# 08_USB_OTG_POWER.net
KiCad netlist of a schematic drawn in Altium Designer
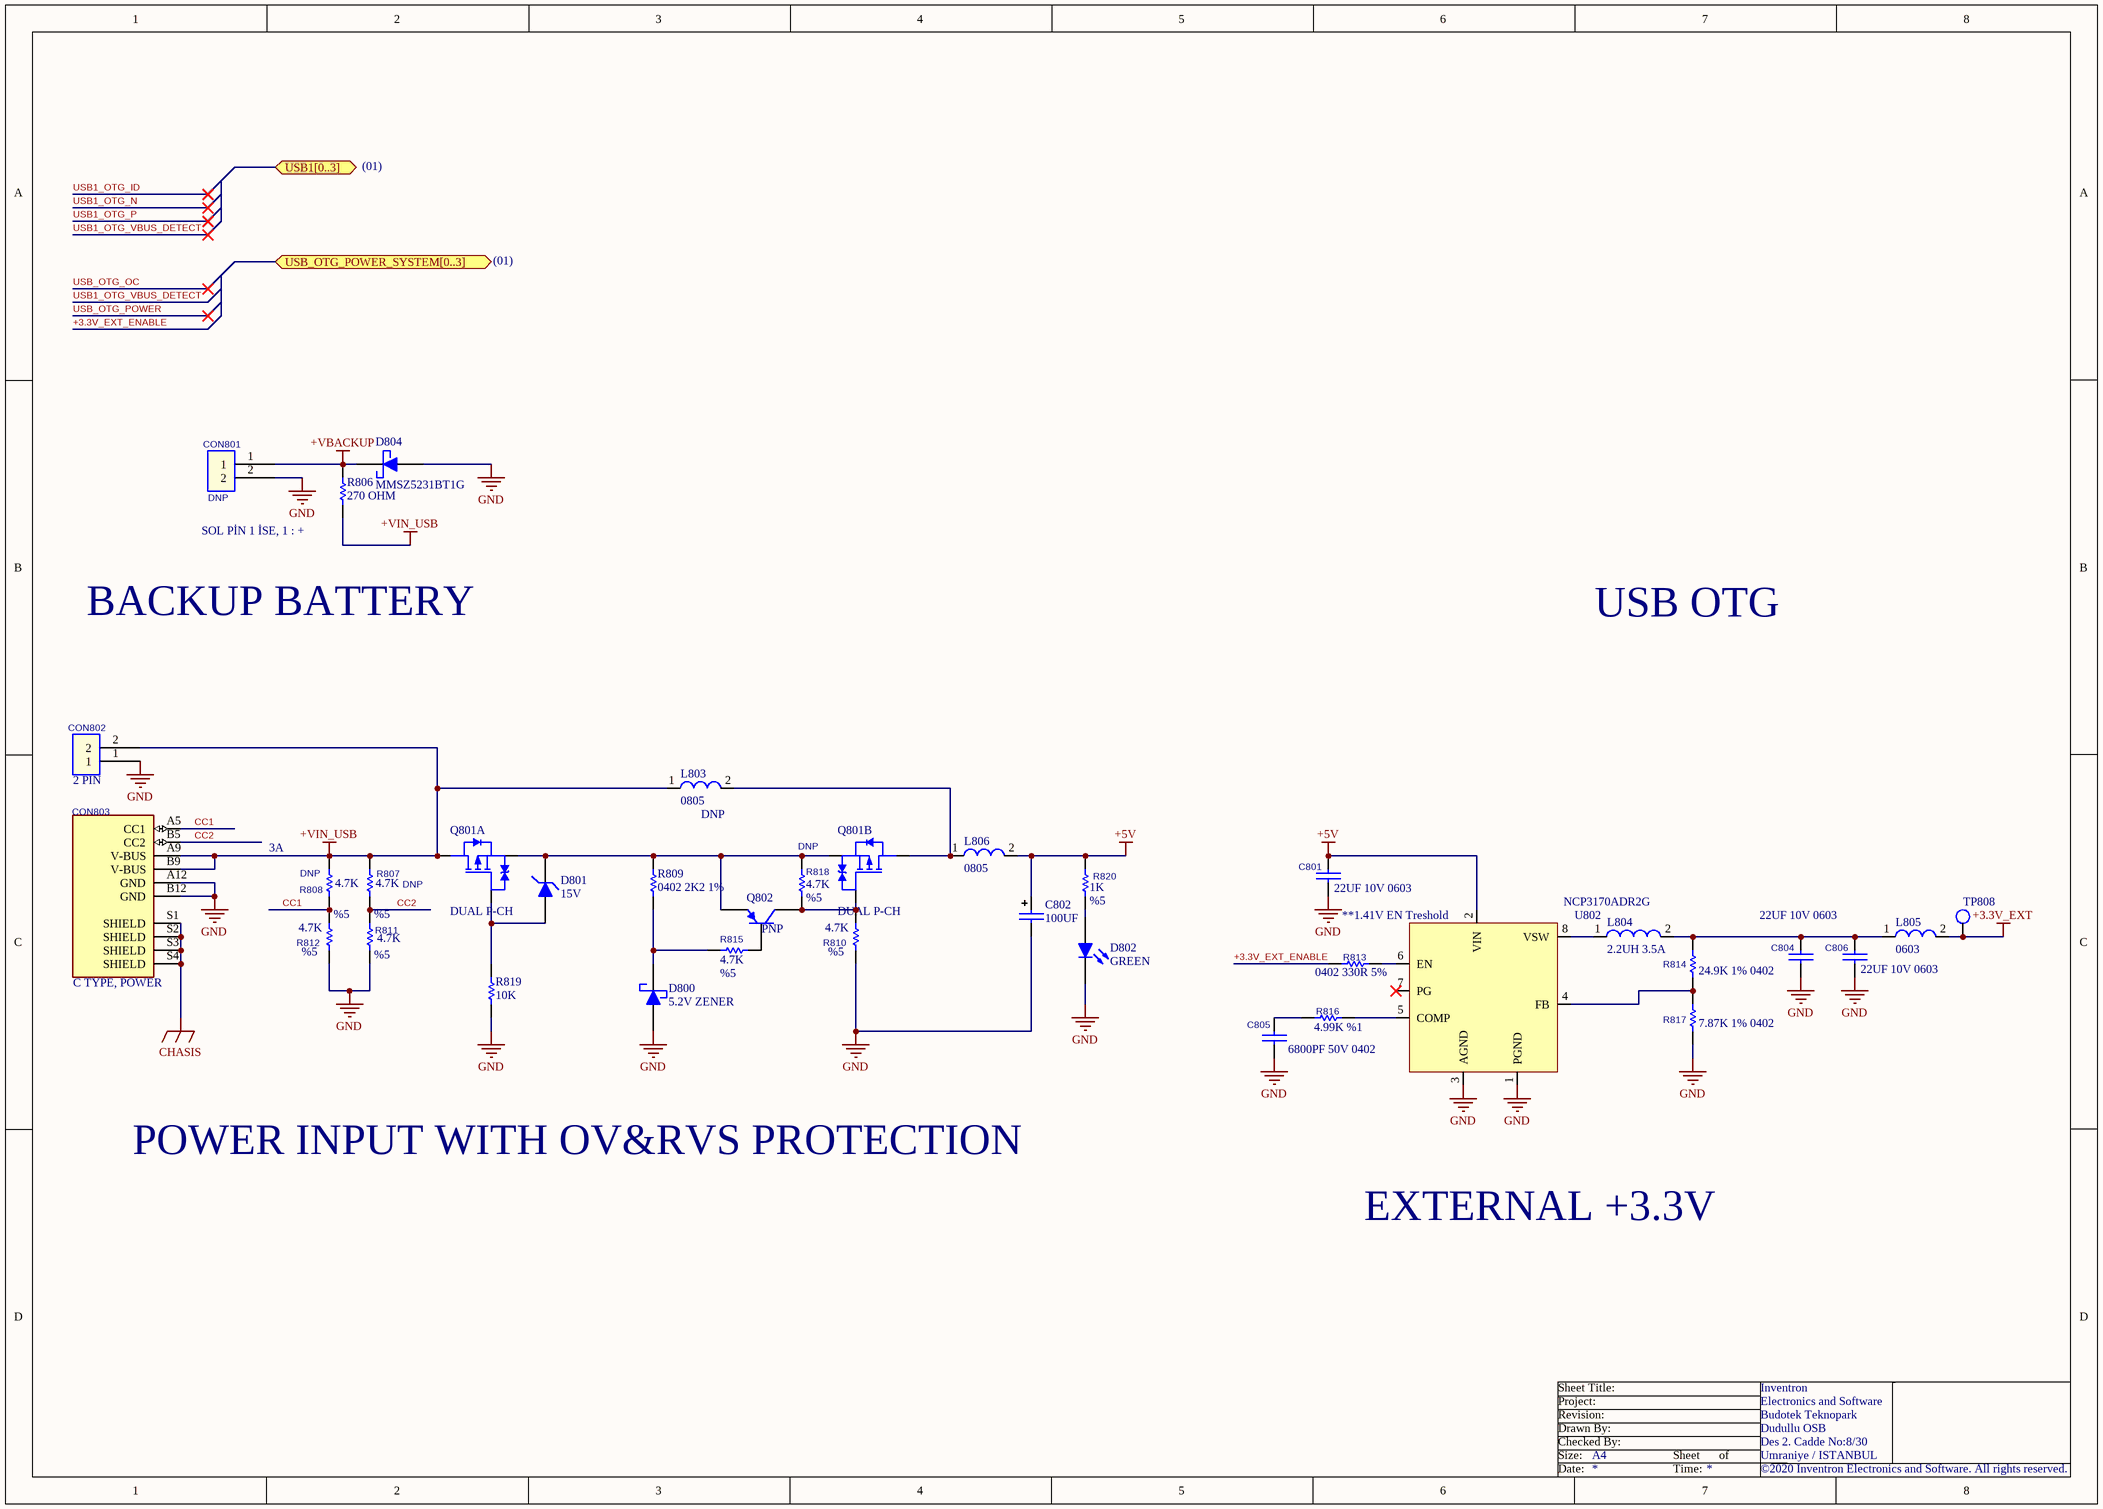
[diagram p0: 08 USB OTG & POWER.SchDoc]

(export (version "E")
  (design (tool "Eeschema 10.0.6"))
  (components
    (comp (ref "C801")
      (value "22UF 10V 0603")
      (footprint "0603_CC")
      (description "±20% 10V Ceramic Capacitor X5R 0603 (1608 Metric)")
      (fields (field (name "CREATED BY") "E.E") (field (name "CHECKED BY") "*"))
      (libsource (lib "ARETE_SCH") (part "CAP-C1608X5R1A226M080AC"))
    )
    (comp (ref "C802")
      (value "100UF")
      (footprint "UWR1A101MCL1GB")
      (description "CAP ALUM 100UF 20% 10V SMD")
      (fields (field (name "CREATED BY") "EE") (field (name "CHECKED BY") "*"))
      (libsource (lib "ARETE_V2_SCH") (part "CAP-UWR1A101MCL1GB"))
    )
    (comp (ref "C804")
      (value "22UF 10V 0603")
      (footprint "0603_CC")
      (description "±20% 10V Ceramic Capacitor X5R 0603 (1608 Metric)")
      (fields (field (name "CREATED BY") "E.E") (field (name "CHECKED BY") "*"))
      (libsource (lib "ARETE_SCH") (part "CAP-C1608X5R1A226M080AC"))
    )
    (comp (ref "C805")
      (value "6800PF 50V 0402")
      (footprint "0402_CC")
      (description "6800pF ±10% 50V Ceramic Capacitor X7R 0402 (1005 Metric)")
      (fields (field (name "CREATED BY") "E.E") (field (name "CHECKED BY") "*"))
      (libsource (lib "ARETE_SCH") (part "CAP-CL05B682KB5NNNC"))
    )
    (comp (ref "C806")
      (value "22UF 10V 0603")
      (footprint "0603_CC")
      (description "±20% 10V Ceramic Capacitor X5R 0603 (1608 Metric)")
      (fields (field (name "CREATED BY") "E.E") (field (name "CHECKED BY") "*"))
      (libsource (lib "ARETE_SCH") (part "CAP-C1608X5R1A226M080AC"))
    )
    (comp (ref "CON801")
      (value "CON-B2B-PH-K-S(LF)(SN)")
      (footprint "B2B-PH-K-S")
      (description "CONN HEADER VERT 2POS 2MM")
      (fields
        (field (name "ASSY_OPT") "DNP")
        (field (name "CREATED BY") "LA")
        (field (name "CHECKED BY") "*")
      )
      (libsource (lib "ARETE_L") (part "CON-B2B-PH-K-S(LF)(SN)"))
    )
    (comp (ref "CON802")
      (value "2 PIN")
      (footprint "640456-2")
      (description "CONN HEADER VERT 2POS 2.54MM")
      (fields (field (name "CREATED BY") "LA") (field (name "CHECKED BY") "*"))
      (libsource (lib "ARETE_L") (part "CON-640456-2"))
    )
    (comp (ref "CON803")
      (value "C TYPE, POWER")
      (footprint "CUI_UJC-HP-3-SMT-TR")
      (description "USB JACK, C TYPE, POWER ONLY, 6")
      (fields (field (name "CREATED BY") "E.E") (field (name "CHECKED BY") "*"))
      (libsource (lib "ARETE_SCH") (part "0-CON-UJC-HP-3-SMT-TR"))
    )
    (comp (ref "D800")
      (value "5.2V ZENER")
      (footprint "SOD-323")
      (description "DIODE ZENER 5.1V 320MW SOD323")
      (fields (field (name "CREATED BY") "EE") (field (name "CHECKED BY") "*"))
      (libsource (lib "ARETE_V2_SCH") (part "DIODE-PZU5.1B2A,115"))
    )
    (comp (ref "D801")
      (value "15V")
      (footprint "SOD-323")
      (description "DIODE ZENER 15V 400MW SOD323")
      (fields (field (name "CREATED BY") "LA") (field (name "CHECKED BY") "*"))
      (libsource (lib "ARETE_V2_SCH") (part "DIODE-PDZ15B,115"))
    )
    (comp (ref "D802")
      (value "GREEN")
      (footprint "0603_LED")
      (description "LED SMD 0603 SUPER GREEN")
      (fields (field (name "CREATED BY") "*") (field (name "CHECKED BY") "*"))
      (libsource (lib "ARETE_SCH") (part "LED-LTST-C190KRKT"))
    )
    (comp (ref "D804")
      (value "MMSZ5231BT1G")
      (footprint "SOD-123")
      (description "DIODE ZENER 5.1V 500MW SOD123")
      (fields (field (name "CREATED BY") "EE") (field (name "CHECKED BY") "*"))
      (libsource (lib "ARETE_SCH") (part "DIODE-MMSZ5231BT1G"))
    )
    (comp (ref "L803")
      (value "0805")
      (footprint "0805")
      (description "0OHM 0805")
      (fields
        (field (name "ASSY_OPT") "DNP")
        (field (name "CREATED BY") "EE")
        (field (name "CHECKED BY") "*")
      )
      (libsource (lib "ARETE_V2_SCH") (part "IND-FERRITE (RES 0 OHM) 0805"))
    )
    (comp (ref "L804")
      (value "2.2UH 3.5A")
      (footprint "IND-NRS5030T2R2NMGJ")
      (description "Shielded Wirewound Inductor 23mOhm Nonstandard")
      (fields (field (name "CREATED BY") "E.E") (field (name "CHECKED BY") "*"))
      (libsource (lib "ARETE_SCH") (part "IND-NRS5030T2R2NMGJ"))
    )
    (comp (ref "L805")
      (value "0603")
      (footprint "0603_RES")
      (description "0OHM 0603")
      (fields (field (name "CREATED BY") "EE") (field (name "CHECKED BY") "*"))
      (libsource (lib "ARETE_SCH") (part "IND-FERRITE (RES 0 OHM) 0603"))
    )
    (comp (ref "L806")
      (value "0805")
      (footprint "0805")
      (description "0OHM 0805")
      (fields (field (name "CREATED BY") "EE") (field (name "CHECKED BY") "*"))
      (libsource (lib "ARETE_V2_SCH") (part "IND-FERRITE (RES 0 OHM) 0805"))
    )
    (comp (ref "Q801")
      (value "DUAL P-CH")
      (footprint "SO-8 - DUAL MOS - NAMED")
      (description "MOSFET 2P-CH 30V 6A SO-8")
      (fields (field (name "CREATED BY") "*") (field (name "CHECKED BY") "*"))
      (libsource (lib "ARETE_V2_SCH") (part "MOS-P-DMP3028LSD-13"))
    )
    (comp (ref "Q802")
      (value "PNP")
      (footprint "SOT23")
      (description "TRANS PNP 65V 0.1A SOT-23")
      (fields (field (name "CREATED BY") "LA") (field (name "CHECKED BY") "*"))
      (libsource (lib "ARETE_V2_SCH") (part "TRANSISTOR-BC856"))
    )
    (comp (ref "R806")
      (value "270 OHM")
      (footprint "0603_RES")
      (description "RES SMD 270 OHM 5% 1/10W 0603")
      (fields (field (name "CREATED BY") "EE") (field (name "CHECKED BY") "*"))
      (libsource (lib "ARETE_SCH") (part "RES-RC0603JR-07270RL"))
    )
    (comp (ref "R807")
      (value "4.7K")
      (footprint "0402_RES")
      (description "RES 4.7K OHM 5% 1/16W 0402")
      (fields
        (field (name "ASSY_OPT") "DNP")
        (field (name "TOLERANCE") "%5")
        (field (name "CREATED BY") "LA")
        (field (name "CHECKED BY") "*")
      )
      (libsource (lib "ARETE_SCH") (part "RES-4.7K"))
    )
    (comp (ref "R808")
      (value "4.7K")
      (footprint "0402_RES")
      (description "RES 4.7K OHM 5% 1/16W 0402")
      (fields
        (field (name "ASSY_OPT") "DNP")
        (field (name "TOLERANCE") "%5")
        (field (name "CREATED BY") "LA")
        (field (name "CHECKED BY") "*")
      )
      (libsource (lib "ARETE_SCH") (part "RES-4.7K"))
    )
    (comp (ref "R809")
      (value "0402 2K2 1%")
      (footprint "0402_RES")
      (fields (field (name "CREATED BY") "E.E") (field (name "CHECKED BY") "*"))
      (libsource (lib "ARETE_V2_SCH") (part "RES-CRGCQ0402F2K2"))
    )
    (comp (ref "R810")
      (value "4.7K")
      (footprint "0402_RES")
      (description "RES 4.7K OHM 5% 1/16W 0402")
      (fields
        (field (name "TOLERANCE") "%5")
        (field (name "CREATED BY") "LA")
        (field (name "CHECKED BY") "*")
      )
      (libsource (lib "ARETE_SCH") (part "RES-4.7K"))
    )
    (comp (ref "R811")
      (value "4.7K")
      (footprint "0402_RES")
      (description "RES 4.7K OHM 5% 1/16W 0402")
      (fields
        (field (name "TOLERANCE") "%5")
        (field (name "CREATED BY") "LA")
        (field (name "CHECKED BY") "*")
      )
      (libsource (lib "ARETE_SCH") (part "RES-4.7K"))
    )
    (comp (ref "R812")
      (value "4.7K")
      (footprint "0402_RES")
      (description "RES 4.7K OHM 5% 1/16W 0402")
      (fields
        (field (name "TOLERANCE") "%5")
        (field (name "CREATED BY") "LA")
        (field (name "CHECKED BY") "*")
      )
      (libsource (lib "ARETE_SCH") (part "RES-4.7K"))
    )
    (comp (ref "R813")
      (value "0402 330R 5%")
      (footprint "0402_RES")
      (fields
        (field (name "TOLERANCE") "%5")
        (field (name "CREATED BY") "E.E")
        (field (name "CHECKED BY") "*")
      )
      (libsource (lib "ARETE_SCH") (part "RES-CRGCQ0402J330R"))
    )
    (comp (ref "R814")
      (value "24.9K 1% 0402")
      (footprint "0402_RES")
      (description "24.9 ±1% 0.063W, 1/16W Chip Resistor 0402 (1005 Metric) - Thick Film")
      (fields (field (name "CREATED BY") "E.E") (field (name "CHECKED BY") "*"))
      (libsource (lib "ARETE_SCH") (part "RES-RC0402FR-0724K9L"))
    )
    (comp (ref "R815")
      (value "4.7K")
      (footprint "0402_RES")
      (description "RES 4.7K OHM 5% 1/16W 0402")
      (fields
        (field (name "TOLERANCE") "%5")
        (field (name "CREATED BY") "LA")
        (field (name "CHECKED BY") "*")
      )
      (libsource (lib "ARETE_SCH") (part "RES-4.7K"))
    )
    (comp (ref "R816")
      (value "4.99K %1")
      (footprint "0603_RES")
      (description "RES 4.99K OHM %1 1/10W 0603")
      (fields (field (name "CREATED BY") "LA") (field (name "CHECKED BY") "*"))
      (libsource (lib "ARETE_SCH") (part "RES-RC0603FR-074K99L"))
    )
    (comp (ref "R817")
      (value "7.87K 1% 0402")
      (footprint "0402_RES")
      (description "7.87 kOhms ±1% 0.063W, 1/16W Chip Resistor 0402 (1005 Metric) Automotive AEC-Q200 Thick Film")
      (fields (field (name "CREATED BY") "EE") (field (name "CHECKED BY") "*"))
      (libsource (lib "ARETE_SCH") (part "RES-CRCW04027K87FKED"))
    )
    (comp (ref "R818")
      (value "4.7K")
      (footprint "0402_RES")
      (description "RES 4.7K OHM 5% 1/16W 0402")
      (fields
        (field (name "ASSY_OPT") "DNP")
        (field (name "TOLERANCE") "%5")
        (field (name "CREATED BY") "LA")
        (field (name "CHECKED BY") "*")
      )
      (libsource (lib "ARETE_SCH") (part "RES-4.7K"))
    )
    (comp (ref "R819")
      (value "10K")
      (footprint "0805")
      (description "RES SMD 10K 5% 0805")
      (fields (field (name "CREATED BY") "*") (field (name "CHECKED BY") "*"))
      (libsource (lib "ARETE_V2_SCH") (part "RES-0805S8J0103TDE"))
    )
    (comp (ref "R820")
      (value "1K")
      (footprint "0402_RES")
      (description "RES 1K OHM 5% 1/16W 0402")
      (fields
        (field (name "TOLERANCE") "%5")
        (field (name "CREATED BY") "LA")
        (field (name "CHECKED BY") "*")
      )
      (libsource (lib "ARETE_SCH") (part "RES-RMCF0402JT1K00"))
    )
    (comp (ref "TP808")
      (value "TEST POINT 35")
      (footprint "testpoint_35mil")
      (libsource (lib "ARETE_SCH") (part "TEST POINT 35"))
    )
    (comp (ref "U802")
      (value "NCP3170ADR2G")
      (footprint "IC-NCP3170ADR2G")
      (description "Buck Regulator, Switching, PWM, 3.0 A")
      (fields (field (name "CREATED BY") "E.E") (field (name "CHECKED BY") "*"))
      (libsource (lib "ARETE_SCH") (part "IC-NCP3170ADR2G"))
    )
  )
  (nets
    (net (code "9") (name "+3.3V_EXT") (class "Default")
      (node (ref "L805") (pin "2") (pinfunction "2_2") (pintype "passive"))
      (node (ref "TP808") (pin "1") (pinfunction "1_1") (pintype "passive"))
    )
    (net (code "10") (name "+5V") (class "Default")
      (node (ref "C801") (pin "1") (pinfunction "1_1") (pintype "passive"))
      (node (ref "C802") (pin "1") (pinfunction "1_1") (pintype "passive"))
      (node (ref "L806") (pin "2") (pinfunction "2_2") (pintype "passive"))
      (node (ref "R820") (pin "1") (pinfunction "1_1") (pintype "passive"))
      (node (ref "U802") (pin "2") (pinfunction "VIN_2") (pintype "passive"))
    )
    (net (code "11") (name "+VBACKUP") (class "Default")
      (node (ref "CON801") (pin "1") (pinfunction "1_1") (pintype "passive"))
      (node (ref "D804") (pin "K") (pinfunction "K_K") (pintype "passive"))
      (node (ref "R806") (pin "1") (pinfunction "1_1") (pintype "passive"))
    )
    (net (code "12") (name "+VIN_USB") (class "Default")
      (node (ref "CON802") (pin "2") (pinfunction "2_2") (pintype "passive"))
      (node (ref "CON803") (pin "A9") (pinfunction "V-BUS_A9") (pintype "power_in"))
      (node (ref "CON803") (pin "B9") (pinfunction "V-BUS_B9") (pintype "power_in"))
      (node (ref "L803") (pin "1") (pinfunction "1_1") (pintype "passive"))
      (node (ref "Q801") (pin "D1") (pinfunction "D1_D1") (pintype "passive"))
      (node (ref "R806") (pin "2") (pinfunction "2_2") (pintype "passive"))
      (node (ref "R807") (pin "1") (pinfunction "1_1") (pintype "passive"))
      (node (ref "R808") (pin "1") (pinfunction "1_1") (pintype "passive"))
    )
    (net (code "13") (name "/+3.3V_EXT_ENABLE") (class "Default")
      (node (ref "R813") (pin "1") (pinfunction "1_1") (pintype "passive"))
    )
    (net (code "14") (name "/CC1") (class "Default")
      (node (ref "CON803") (pin "A5") (pinfunction "CC1_A5") (pintype "bidirectional"))
      (node (ref "R808") (pin "2") (pinfunction "2_2") (pintype "passive"))
      (node (ref "R812") (pin "1") (pinfunction "1_1") (pintype "passive"))
    )
    (net (code "15") (name "/CC2") (class "Default")
      (node (ref "CON803") (pin "B5") (pinfunction "CC2_B5") (pintype "bidirectional"))
      (node (ref "R807") (pin "2") (pinfunction "2_2") (pintype "passive"))
      (node (ref "R811") (pin "1") (pinfunction "1_1") (pintype "passive"))
    )
    (net (code "24") (name "CHASIS") (class "Default")
      (node (ref "CON803") (pin "S1") (pinfunction "SHIELD_S1") (pintype "passive"))
      (node (ref "CON803") (pin "S2") (pinfunction "SHIELD_S2") (pintype "passive"))
      (node (ref "CON803") (pin "S3") (pinfunction "SHIELD_S3") (pintype "passive"))
      (node (ref "CON803") (pin "S4") (pinfunction "SHIELD_S4") (pintype "passive"))
    )
    (net (code "25") (name "GND") (class "Default")
      (node (ref "C801") (pin "2") (pinfunction "2_2") (pintype "passive"))
      (node (ref "C802") (pin "2") (pinfunction "2_2") (pintype "passive"))
      (node (ref "C804") (pin "2") (pinfunction "2_2") (pintype "passive"))
      (node (ref "C805") (pin "2") (pinfunction "2_2") (pintype "passive"))
      (node (ref "C806") (pin "2") (pinfunction "2_2") (pintype "passive"))
      (node (ref "CON801") (pin "2") (pinfunction "2_2") (pintype "passive"))
      (node (ref "CON802") (pin "1") (pinfunction "1_1") (pintype "passive"))
      (node (ref "CON803") (pin "A12") (pinfunction "GND_A12") (pintype "power_in"))
      (node (ref "CON803") (pin "B12") (pinfunction "GND_B12") (pintype "power_in"))
      (node (ref "D800") (pin "A") (pinfunction "A_A") (pintype "passive"))
      (node (ref "D802") (pin "2") (pinfunction "K_2") (pintype "passive"))
      (node (ref "D804") (pin "A") (pinfunction "A_A") (pintype "passive"))
      (node (ref "R810") (pin "2") (pinfunction "2_2") (pintype "passive"))
      (node (ref "R811") (pin "2") (pinfunction "2_2") (pintype "passive"))
      (node (ref "R812") (pin "2") (pinfunction "2_2") (pintype "passive"))
      (node (ref "R817") (pin "1") (pinfunction "1_1") (pintype "passive"))
      (node (ref "R819") (pin "1") (pinfunction "1_1") (pintype "passive"))
      (node (ref "U802") (pin "1") (pinfunction "PGND_1") (pintype "passive"))
      (node (ref "U802") (pin "3") (pinfunction "AGND_3") (pintype "passive"))
    )
    (net (code "26") (name "Net-(C804-Pad1)") (class "Default")
      (node (ref "C804") (pin "1") (pinfunction "1_1") (pintype "passive"))
      (node (ref "C806") (pin "1") (pinfunction "1_1") (pintype "passive"))
      (node (ref "L804") (pin "2") (pinfunction "2_2") (pintype "passive"))
      (node (ref "L805") (pin "1") (pinfunction "1_1") (pintype "passive"))
      (node (ref "R814") (pin "2") (pinfunction "2_2") (pintype "passive"))
    )
    (net (code "27") (name "Net-(C805-Pad1)") (class "Default")
      (node (ref "C805") (pin "1") (pinfunction "1_1") (pintype "passive"))
      (node (ref "R816") (pin "1") (pinfunction "1_1") (pintype "passive"))
    )
    (net (code "28") (name "Net-(D800-PadK)") (class "Default")
      (node (ref "D800") (pin "K") (pinfunction "K_K") (pintype "passive"))
      (node (ref "R809") (pin "1") (pinfunction "1_1") (pintype "passive"))
      (node (ref "R815") (pin "1") (pinfunction "1_1") (pintype "passive"))
    )
    (net (code "29") (name "Net-(D801-PadA)") (class "Default")
      (node (ref "D801") (pin "A") (pinfunction "A_A") (pintype "passive"))
      (node (ref "Q801") (pin "G1") (pinfunction "G1_G1") (pintype "passive"))
      (node (ref "R819") (pin "2") (pinfunction "2_2") (pintype "passive"))
    )
    (net (code "30") (name "Net-(D802-A)") (class "Default")
      (node (ref "D802") (pin "1") (pinfunction "A_1") (pintype "passive"))
      (node (ref "R820") (pin "2") (pinfunction "2_2") (pintype "passive"))
    )
    (net (code "31") (name "Net-(L803-Pad2)") (class "Default")
      (node (ref "L803") (pin "2") (pinfunction "2_2") (pintype "passive"))
      (node (ref "L806") (pin "1") (pinfunction "1_1") (pintype "passive"))
      (node (ref "Q801") (pin "D2") (pinfunction "D2_D2") (pintype "passive"))
    )
    (net (code "32") (name "Net-(Q802-B)") (class "Default")
      (node (ref "Q802") (pin "1") (pinfunction "B_1") (pintype "passive"))
      (node (ref "R815") (pin "2") (pinfunction "2_2") (pintype "passive"))
    )
    (net (code "33") (name "Net-(Q802-C)") (class "Default")
      (node (ref "Q801") (pin "G2") (pinfunction "G2_G2") (pintype "passive"))
      (node (ref "Q802") (pin "3") (pinfunction "C_3") (pintype "passive"))
      (node (ref "R810") (pin "1") (pinfunction "1_1") (pintype "passive"))
      (node (ref "R818") (pin "1") (pinfunction "1_1") (pintype "passive"))
    )
    (net (code "34") (name "Net-(Q802-E)") (class "Default")
      (node (ref "D801") (pin "K") (pinfunction "K_K") (pintype "passive"))
      (node (ref "Q801") (pin "S1") (pinfunction "S1_S1") (pintype "passive"))
      (node (ref "Q801") (pin "S2") (pinfunction "S2_S2") (pintype "passive"))
      (node (ref "Q802") (pin "2") (pinfunction "E_2") (pintype "passive"))
      (node (ref "R809") (pin "2") (pinfunction "2_2") (pintype "passive"))
      (node (ref "R818") (pin "2") (pinfunction "2_2") (pintype "passive"))
    )
    (net (code "35") (name "Net-(U802-COMP)") (class "Default")
      (node (ref "R816") (pin "2") (pinfunction "2_2") (pintype "passive"))
      (node (ref "U802") (pin "5") (pinfunction "COMP_5") (pintype "passive"))
    )
    (net (code "36") (name "Net-(U802-EN)") (class "Default")
      (node (ref "R813") (pin "2") (pinfunction "2_2") (pintype "passive"))
      (node (ref "U802") (pin "6") (pinfunction "EN_6") (pintype "passive"))
    )
    (net (code "37") (name "Net-(U802-FB)") (class "Default")
      (node (ref "R814") (pin "1") (pinfunction "1_1") (pintype "passive"))
      (node (ref "R817") (pin "2") (pinfunction "2_2") (pintype "passive"))
      (node (ref "U802") (pin "4") (pinfunction "FB_4") (pintype "passive"))
    )
    (net (code "38") (name "Net-(U802-VSW)") (class "Default")
      (node (ref "L804") (pin "1") (pinfunction "1_1") (pintype "passive"))
      (node (ref "U802") (pin "8") (pinfunction "VSW_8") (pintype "passive"))
    )
    (net (code "39") (name "unconnected-(U802-PG-Pad7)") (class "Default")
      (node (ref "U802") (pin "7") (pinfunction "PG_7") (pintype "passive+no_connect"))
    )
  )
)
